# ASBB_MCP25625.net
KiCad netlist of a schematic drawn in Altium Designer
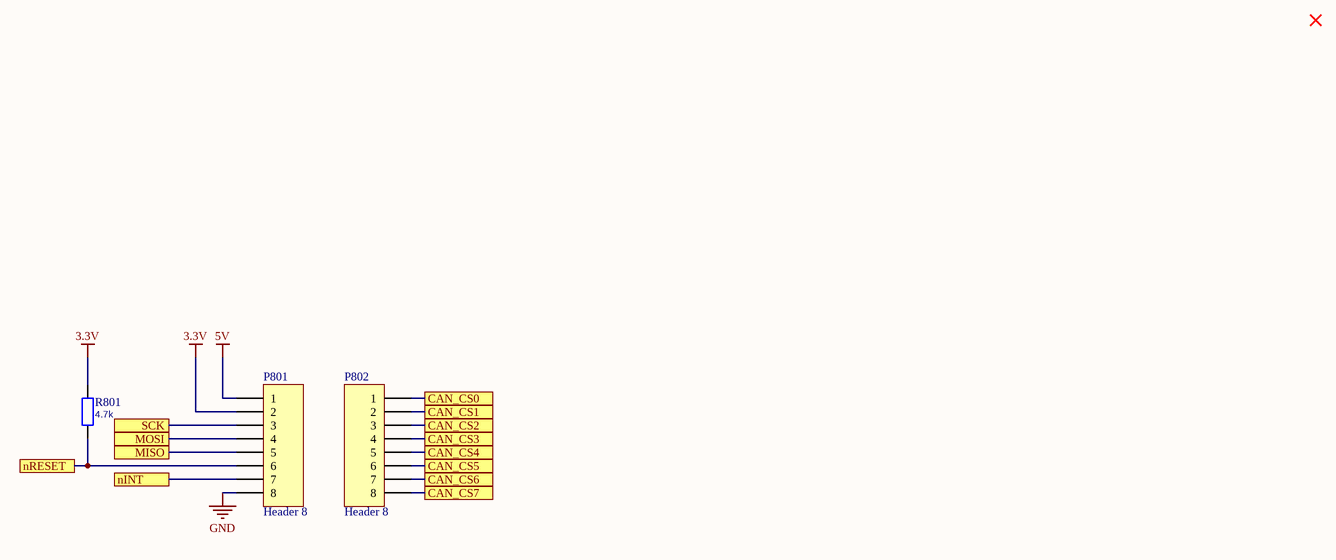
[diagram p0: ASBB_MCP25625.SchDoc]

(export (version "E")
  (design (tool "Eeschema 10.0.6"))
  (components
    (comp (ref "P801")
      (value "Header 8")
      (footprint "HDR1X8")
      (description "Header, 8-Pin")
      (fields (field (name "PUBLISHER") "Altium Limited"))
      (libsource (lib "") (part "Header 8_1"))
    )
    (comp (ref "P802")
      (value "Header 8")
      (footprint "HDR1X8")
      (description "Header, 8-Pin")
      (fields (field (name "PUBLISHER") "Altium Limited"))
      (libsource (lib "Miscellaneous Connectors") (part "Header 8"))
    )
    (comp (ref "R801")
      (value "4.7k")
      (footprint "0603")
      (description "Resistor")
      (fields (field (name "PARTNUMBER") "?"))
      (libsource (lib "FZI") (part "Resistor"))
    )
  )
  (nets
    (net (code "1") (name "/CAN_CS0") (class "Default")
      (node (ref "P802") (pin "1") (pinfunction "1_1") (pintype "passive"))
    )
    (net (code "2") (name "/CAN_CS1") (class "Default")
      (node (ref "P802") (pin "2") (pinfunction "2_2") (pintype "passive"))
    )
    (net (code "3") (name "/CAN_CS2") (class "Default")
      (node (ref "P802") (pin "3") (pinfunction "3_3") (pintype "passive"))
    )
    (net (code "4") (name "/CAN_CS3") (class "Default")
      (node (ref "P802") (pin "4") (pinfunction "4_4") (pintype "passive"))
    )
    (net (code "5") (name "/CAN_CS4") (class "Default")
      (node (ref "P802") (pin "5") (pinfunction "5_5") (pintype "passive"))
    )
    (net (code "6") (name "/CAN_CS5") (class "Default")
      (node (ref "P802") (pin "6") (pinfunction "6_6") (pintype "passive"))
    )
    (net (code "7") (name "/CAN_CS6") (class "Default")
      (node (ref "P802") (pin "7") (pinfunction "7_7") (pintype "passive"))
    )
    (net (code "8") (name "/CAN_CS7") (class "Default")
      (node (ref "P802") (pin "8") (pinfunction "8_8") (pintype "passive"))
    )
    (net (code "9") (name "/MISO") (class "Default")
      (node (ref "P801") (pin "5") (pinfunction "5_5") (pintype "passive"))
    )
    (net (code "10") (name "/MOSI") (class "Default")
      (node (ref "P801") (pin "4") (pinfunction "4_4") (pintype "passive"))
    )
    (net (code "11") (name "/SCK") (class "Default")
      (node (ref "P801") (pin "3") (pinfunction "3_3") (pintype "passive"))
    )
    (net (code "12") (name "/nINT") (class "Default")
      (node (ref "P801") (pin "7") (pinfunction "7_7") (pintype "passive"))
    )
    (net (code "13") (name "/nRESET") (class "Default")
      (node (ref "P801") (pin "6") (pinfunction "6_6") (pintype "passive"))
      (node (ref "R801") (pin "1") (pinfunction "1_1") (pintype "passive"))
    )
    (net (code "14") (name "3.3V") (class "Default")
      (node (ref "P801") (pin "2") (pinfunction "2_2") (pintype "passive"))
      (node (ref "R801") (pin "2") (pinfunction "2_2") (pintype "passive"))
    )
    (net (code "15") (name "5V") (class "Default")
      (node (ref "P801") (pin "1") (pinfunction "1_1") (pintype "passive"))
    )
    (net (code "16") (name "GND") (class "Default")
      (node (ref "P801") (pin "8") (pinfunction "8_8") (pintype "passive"))
    )
  )
)
